# REUN_468349_001_PSU_Board_12B_Interface.net
KiCad netlist of a schematic drawn in Altium Designer
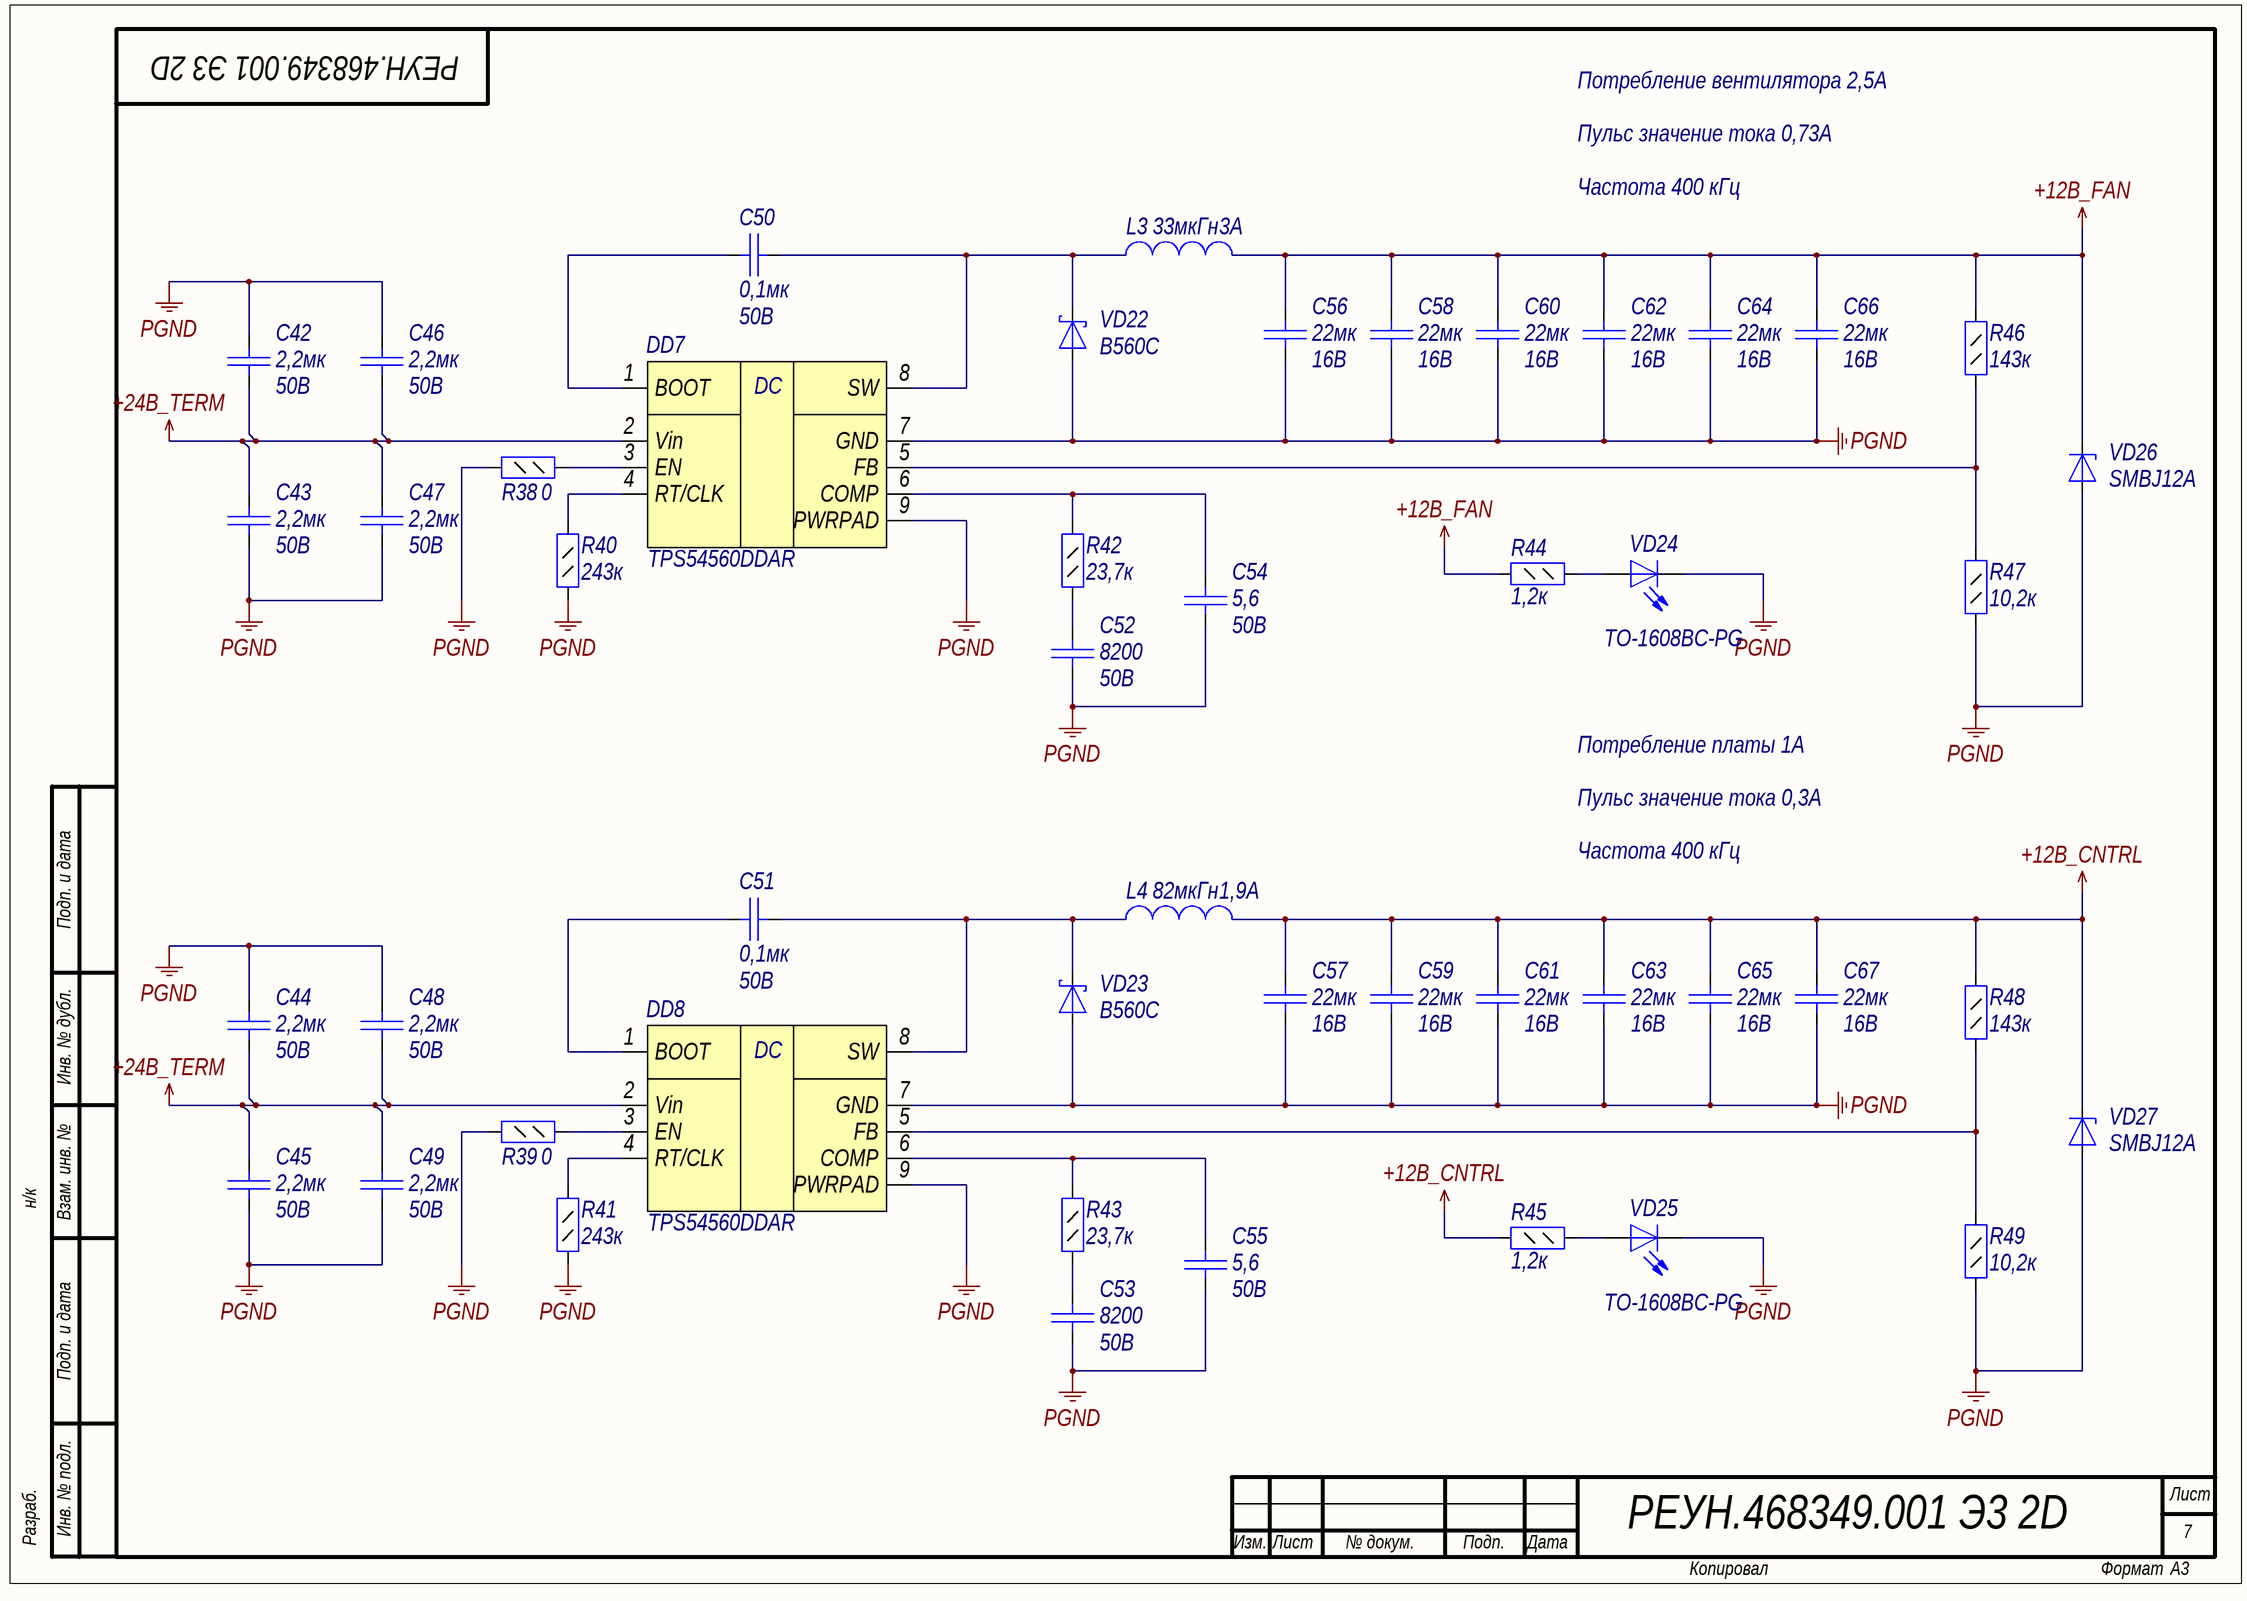
[diagram p0: REUN.468349.001_PSU_Board_12B_Interface.SchDoc]

(export (version "E")
  (design (tool "Eeschema 10.0.6"))
  (components
    (comp (ref "C42")
      (value "2,2мк")
      (footprint "C1206")
      (description "Конденсатор")
      (fields (field (name "VOLTAGE") "50B") (field (name "PART NUMBER") "CL31B225KBHNNNE"))
      (libsource (lib "MOP44") (part "Capacitor"))
    )
    (comp (ref "C43")
      (value "2,2мк")
      (footprint "C1206")
      (description "Конденсатор")
      (fields (field (name "VOLTAGE") "50B") (field (name "PART NUMBER") "CL31B225KBHNNNE"))
      (libsource (lib "MOP44") (part "Capacitor"))
    )
    (comp (ref "C44")
      (value "2,2мк")
      (footprint "C1206")
      (description "Конденсатор")
      (fields (field (name "VOLTAGE") "50B") (field (name "PART NUMBER") "CL31B225KBHNNNE"))
      (libsource (lib "MOP44") (part "Capacitor"))
    )
    (comp (ref "C45")
      (value "2,2мк")
      (footprint "C1206")
      (description "Конденсатор")
      (fields (field (name "VOLTAGE") "50B") (field (name "PART NUMBER") "CL31B225KBHNNNE"))
      (libsource (lib "MOP44") (part "Capacitor"))
    )
    (comp (ref "C46")
      (value "2,2мк")
      (footprint "C1206")
      (description "Конденсатор")
      (fields (field (name "VOLTAGE") "50B") (field (name "PART NUMBER") "CL31B225KBHNNNE"))
      (libsource (lib "MOP44") (part "Capacitor"))
    )
    (comp (ref "C47")
      (value "2,2мк")
      (footprint "C1206")
      (description "Конденсатор")
      (fields (field (name "VOLTAGE") "50B") (field (name "PART NUMBER") "CL31B225KBHNNNE"))
      (libsource (lib "MOP44") (part "Capacitor"))
    )
    (comp (ref "C48")
      (value "2,2мк")
      (footprint "C1206")
      (description "Конденсатор")
      (fields (field (name "VOLTAGE") "50B") (field (name "PART NUMBER") "CL31B225KBHNNNE"))
      (libsource (lib "MOP44") (part "Capacitor"))
    )
    (comp (ref "C49")
      (value "2,2мк")
      (footprint "C1206")
      (description "Конденсатор")
      (fields (field (name "VOLTAGE") "50B") (field (name "PART NUMBER") "CL31B225KBHNNNE"))
      (libsource (lib "MOP44") (part "Capacitor"))
    )
    (comp (ref "C50")
      (value "0,1мк")
      (footprint "C0805")
      (description "Конденсатор")
      (fields (field (name "VOLTAGE") "50B") (field (name "PART NUMBER") "GRM21BR71H104KA01K"))
      (libsource (lib "MOP44") (part "Capacitor"))
    )
    (comp (ref "C51")
      (value "0,1мк")
      (footprint "C0805")
      (description "Конденсатор")
      (fields (field (name "VOLTAGE") "50B") (field (name "PART NUMBER") "GRM21BR71H104KA01K"))
      (libsource (lib "MOP44") (part "Capacitor"))
    )
    (comp (ref "C52")
      (value "8200")
      (footprint "C0805")
      (description "Конденсатор")
      (fields (field (name "VOLTAGE") "50В") (field (name "PART NUMBER") "GRM216R71H822KA01D"))
      (libsource (lib "MOP44") (part "Capacitor"))
    )
    (comp (ref "C53")
      (value "8200")
      (footprint "C0805")
      (description "Конденсатор")
      (fields (field (name "VOLTAGE") "50В") (field (name "PART NUMBER") "GRM216R71H822KA01D"))
      (libsource (lib "MOP44") (part "Capacitor"))
    )
    (comp (ref "C54")
      (value "5,6")
      (footprint "C0805")
      (description "Конденсатор")
      (fields (field (name "VOLTAGE") "50B") (field (name "PART NUMBER") "CL21C5R6CBANNNC"))
      (libsource (lib "MOP44") (part "Capacitor"))
    )
    (comp (ref "C55")
      (value "5,6")
      (footprint "C0805")
      (description "Конденсатор")
      (fields (field (name "VOLTAGE") "50B") (field (name "PART NUMBER") "CL21C5R6CBANNNC"))
      (libsource (lib "MOP44") (part "Capacitor"))
    )
    (comp (ref "C56")
      (value "22мк")
      (footprint "C1210")
      (description "Конденсатор")
      (fields (field (name "VOLTAGE") "16B") (field (name "PART NUMBER") "CL32B226KOJNNNE"))
      (libsource (lib "MOP44") (part "Capacitor"))
    )
    (comp (ref "C57")
      (value "22мк")
      (footprint "C1210")
      (description "Конденсатор")
      (fields (field (name "VOLTAGE") "16B") (field (name "PART NUMBER") "CL32B226KOJNNNE"))
      (libsource (lib "MOP44") (part "Capacitor"))
    )
    (comp (ref "C58")
      (value "22мк")
      (footprint "C1210")
      (description "Конденсатор")
      (fields (field (name "VOLTAGE") "16B") (field (name "PART NUMBER") "CL32B226KOJNNNE"))
      (libsource (lib "MOP44") (part "Capacitor"))
    )
    (comp (ref "C59")
      (value "22мк")
      (footprint "C1210")
      (description "Конденсатор")
      (fields (field (name "VOLTAGE") "16B") (field (name "PART NUMBER") "CL32B226KOJNNNE"))
      (libsource (lib "MOP44") (part "Capacitor"))
    )
    (comp (ref "C60")
      (value "22мк")
      (footprint "C1210")
      (description "Конденсатор")
      (fields (field (name "VOLTAGE") "16B") (field (name "PART NUMBER") "CL32B226KOJNNNE"))
      (libsource (lib "MOP44") (part "Capacitor"))
    )
    (comp (ref "C61")
      (value "22мк")
      (footprint "C1210")
      (description "Конденсатор")
      (fields (field (name "VOLTAGE") "16B") (field (name "PART NUMBER") "CL32B226KOJNNNE"))
      (libsource (lib "MOP44") (part "Capacitor"))
    )
    (comp (ref "C62")
      (value "22мк")
      (footprint "C1210")
      (description "Конденсатор")
      (fields (field (name "VOLTAGE") "16B") (field (name "PART NUMBER") "CL32B226KOJNNNE"))
      (libsource (lib "MOP44") (part "Capacitor"))
    )
    (comp (ref "C63")
      (value "22мк")
      (footprint "C1210")
      (description "Конденсатор")
      (fields (field (name "VOLTAGE") "16B") (field (name "PART NUMBER") "CL32B226KOJNNNE"))
      (libsource (lib "MOP44") (part "Capacitor"))
    )
    (comp (ref "C64")
      (value "22мк")
      (footprint "C1210")
      (description "Конденсатор")
      (fields (field (name "VOLTAGE") "16B") (field (name "PART NUMBER") "CL32B226KOJNNNE"))
      (libsource (lib "MOP44") (part "Capacitor"))
    )
    (comp (ref "C65")
      (value "22мк")
      (footprint "C1210")
      (description "Конденсатор")
      (fields (field (name "VOLTAGE") "16B") (field (name "PART NUMBER") "CL32B226KOJNNNE"))
      (libsource (lib "MOP44") (part "Capacitor"))
    )
    (comp (ref "C66")
      (value "22мк")
      (footprint "C1210")
      (description "Конденсатор")
      (fields (field (name "VOLTAGE") "16B") (field (name "PART NUMBER") "CL32B226KOJNNNE"))
      (libsource (lib "MOP44") (part "Capacitor"))
    )
    (comp (ref "C67")
      (value "22мк")
      (footprint "C1210")
      (description "Конденсатор")
      (fields (field (name "VOLTAGE") "16B") (field (name "PART NUMBER") "CL32B226KOJNNNE"))
      (libsource (lib "MOP44") (part "Capacitor"))
    )
    (comp (ref "DD7")
      (value "TPS54560DDAR")
      (footprint "SO Powerpad8")
      (description "5-A, Wide Input Range, Step-Down Converter")
      (fields (field (name "MANUFACTURER") "Texas Instruments"))
      (libsource (lib "MOP44") (part "TPS54560"))
    )
    (comp (ref "DD8")
      (value "TPS54560DDAR")
      (footprint "SO Powerpad8")
      (description "5-A, Wide Input Range, Step-Down Converter")
      (fields (field (name "MANUFACTURER") "Texas Instruments"))
      (libsource (lib "MOP44") (part "TPS54560"))
    )
    (comp (ref "L3")
      (value "33мкГн")
      (footprint "IND_12.5x12.5")
      (description "EMI Suppression Filter")
      (fields
        (field (name "RATED CURRENT") "3A")
        (field (name "PART NUMBER") "B82477G4333M000")
        (field (name "Comment") "Inductor")
      )
      (libsource (lib "MOP44") (part "Inductor"))
    )
    (comp (ref "L4")
      (value "82мкГн")
      (footprint "IND_12.5x12.5")
      (description "EMI Suppression Filter")
      (fields
        (field (name "RATED CURRENT") "1,9A")
        (field (name "PART NUMBER") "B82477G4823M000")
        (field (name "Comment") "Inductor")
      )
      (libsource (lib "MOP44") (part "Inductor"))
    )
    (comp (ref "R38")
      (value "0")
      (footprint "R0805")
      (description "Резистор")
      (fields (field (name "PART NUMBER") "RC0805FR-070RL") (field (name "POWER") "0,125Вт"))
      (libsource (lib "REUN.468349.001_PSU_Board") (part "res25"))
    )
    (comp (ref "R39")
      (value "0")
      (footprint "R0805")
      (description "Резистор")
      (fields (field (name "PART NUMBER") "RC0805FR-070RL") (field (name "POWER") "0,125Вт"))
      (libsource (lib "REUN.468349.001_PSU_Board") (part "res25"))
    )
    (comp (ref "R40")
      (value "243к")
      (footprint "R0805")
      (description "Резистор")
      (fields (field (name "PART NUMBER") "RC0805FR-07243KL") (field (name "POWER") "0,125Вт"))
      (libsource (lib "MOP44") (part "Resistor_0,125Вт"))
    )
    (comp (ref "R41")
      (value "243к")
      (footprint "R0805")
      (description "Резистор")
      (fields (field (name "PART NUMBER") "RC0805FR-07243KL") (field (name "POWER") "0,125Вт"))
      (libsource (lib "MOP44") (part "Resistor_0,125Вт"))
    )
    (comp (ref "R42")
      (value "23,7к")
      (footprint "R0805")
      (description "Резистор")
      (fields (field (name "PART NUMBER") "RC0805FR-0723K7L") (field (name "POWER") "0,125Вт"))
      (libsource (lib "MOP44") (part "Resistor_0,125Вт"))
    )
    (comp (ref "R43")
      (value "23,7к")
      (footprint "R0805")
      (description "Резистор")
      (fields (field (name "PART NUMBER") "RC0805FR-0723K7L") (field (name "POWER") "0,125Вт"))
      (libsource (lib "MOP44") (part "Resistor_0,125Вт"))
    )
    (comp (ref "R44")
      (value "1,2к")
      (footprint "R0805")
      (description "Резистор")
      (fields (field (name "PART NUMBER") "RC0805FR-071K2") (field (name "POWER") "0,125Вт"))
      (libsource (lib "") (part "Resistor_0,125Вт_1"))
    )
    (comp (ref "R45")
      (value "1,2к")
      (footprint "R0805")
      (description "Резистор")
      (fields (field (name "PART NUMBER") "RC0805FR-071K2") (field (name "POWER") "0,125Вт"))
      (libsource (lib "") (part "Resistor_0,125Вт_1"))
    )
    (comp (ref "R46")
      (value "143к")
      (footprint "R0805")
      (description "Резистор")
      (fields (field (name "PART NUMBER") "RC0805FR-07143KL") (field (name "POWER") "0,125Вт"))
      (libsource (lib "MOP44") (part "Resistor_0,125Вт"))
    )
    (comp (ref "R47")
      (value "10,2к")
      (footprint "R0805")
      (description "Резистор")
      (fields (field (name "PART NUMBER") "RC0805FR-0710K2L") (field (name "POWER") "0,125Вт"))
      (libsource (lib "MOP44") (part "Resistor_0,125Вт"))
    )
    (comp (ref "R48")
      (value "143к")
      (footprint "R0805")
      (description "Резистор")
      (fields (field (name "PART NUMBER") "RC0805FR-07143KL") (field (name "POWER") "0,125Вт"))
      (libsource (lib "MOP44") (part "Resistor_0,125Вт"))
    )
    (comp (ref "R49")
      (value "10,2к")
      (footprint "R0805")
      (description "Резистор")
      (fields (field (name "PART NUMBER") "RC0805FR-0710K2L") (field (name "POWER") "0,125Вт"))
      (libsource (lib "MOP44") (part "Resistor_0,125Вт"))
    )
    (comp (ref "VD22")
      (value "B560C")
      (footprint "SMC")
      (description "Диод Шоттки")
      (libsource (lib "MOP44") (part "DiodeSchottky"))
    )
    (comp (ref "VD23")
      (value "B560C")
      (footprint "SMC")
      (description "Диод Шоттки")
      (libsource (lib "MOP44") (part "DiodeSchottky"))
    )
    (comp (ref "VD24")
      (value "TO-1608BC-PG")
      (footprint "L_0603_GREEN")
      (description "Светодиод")
      (libsource (lib "MOP44") (part "LED"))
    )
    (comp (ref "VD25")
      (value "TO-1608BC-PG")
      (footprint "L_0603_GREEN")
      (description "Светодиод")
      (libsource (lib "MOP44") (part "LED"))
    )
    (comp (ref "VD26")
      (value "SMBJ12A")
      (footprint "SMB")
      (description "Cтабилитрон (лавинный выпрямительный диод) односторонний")
      (libsource (lib "MOP44") (part "DiodeZener"))
    )
    (comp (ref "VD27")
      (value "SMBJ12A")
      (footprint "SMB")
      (description "Cтабилитрон (лавинный выпрямительный диод) односторонний")
      (libsource (lib "MOP44") (part "DiodeZener"))
    )
  )
  (nets
    (net (code "1") (name "+12B_CNTRL") (class "Default")
      (node (ref "C57") (pin "2") (pinfunction "2_2") (pintype "passive"))
      (node (ref "C59") (pin "2") (pinfunction "2_2") (pintype "passive"))
      (node (ref "C61") (pin "2") (pinfunction "2_2") (pintype "passive"))
      (node (ref "C63") (pin "2") (pinfunction "2_2") (pintype "passive"))
      (node (ref "C65") (pin "2") (pinfunction "2_2") (pintype "passive"))
      (node (ref "C67") (pin "2") (pinfunction "2_2") (pintype "passive"))
      (node (ref "L4") (pin "2") (pinfunction "2_2") (pintype "passive"))
      (node (ref "R45") (pin "2") (pinfunction "2_2") (pintype "passive"))
      (node (ref "R48") (pin "2") (pinfunction "2_2") (pintype "passive"))
      (node (ref "VD27") (pin "1") (pinfunction "K_1") (pintype "passive"))
    )
    (net (code "2") (name "+12B_FAN") (class "Default")
      (node (ref "C56") (pin "2") (pinfunction "2_2") (pintype "passive"))
      (node (ref "C58") (pin "2") (pinfunction "2_2") (pintype "passive"))
      (node (ref "C60") (pin "2") (pinfunction "2_2") (pintype "passive"))
      (node (ref "C62") (pin "2") (pinfunction "2_2") (pintype "passive"))
      (node (ref "C64") (pin "2") (pinfunction "2_2") (pintype "passive"))
      (node (ref "C66") (pin "2") (pinfunction "2_2") (pintype "passive"))
      (node (ref "L3") (pin "2") (pinfunction "2_2") (pintype "passive"))
      (node (ref "R44") (pin "2") (pinfunction "2_2") (pintype "passive"))
      (node (ref "R46") (pin "2") (pinfunction "2_2") (pintype "passive"))
      (node (ref "VD26") (pin "1") (pinfunction "K_1") (pintype "passive"))
    )
    (net (code "3") (name "+24B_TERM") (class "Default")
      (node (ref "C42") (pin "1") (pinfunction "1_1") (pintype "passive"))
      (node (ref "C43") (pin "2") (pinfunction "2_2") (pintype "passive"))
      (node (ref "C44") (pin "1") (pinfunction "1_1") (pintype "passive"))
      (node (ref "C45") (pin "2") (pinfunction "2_2") (pintype "passive"))
      (node (ref "C46") (pin "1") (pinfunction "1_1") (pintype "passive"))
      (node (ref "C47") (pin "2") (pinfunction "2_2") (pintype "passive"))
      (node (ref "C48") (pin "1") (pinfunction "1_1") (pintype "passive"))
      (node (ref "C49") (pin "2") (pinfunction "2_2") (pintype "passive"))
      (node (ref "DD7") (pin "2") (pinfunction "Vin_2") (pintype "passive"))
      (node (ref "DD8") (pin "2") (pinfunction "Vin_2") (pintype "passive"))
    )
    (net (code "4") (name "Net-(C52-Pad2)") (class "Default")
      (node (ref "C52") (pin "2") (pinfunction "2_2") (pintype "passive"))
      (node (ref "R42") (pin "1") (pinfunction "1_1") (pintype "passive"))
    )
    (net (code "5") (name "Net-(C53-Pad2)") (class "Default")
      (node (ref "C53") (pin "2") (pinfunction "2_2") (pintype "passive"))
      (node (ref "R43") (pin "1") (pinfunction "1_1") (pintype "passive"))
    )
    (net (code "6") (name "Net-(DD7-BOOT)") (class "Default")
      (node (ref "C50") (pin "2") (pinfunction "2_2") (pintype "passive"))
      (node (ref "DD7") (pin "1") (pinfunction "BOOT_1") (pintype "passive"))
    )
    (net (code "7") (name "Net-(DD7-COMP)") (class "Default")
      (node (ref "C54") (pin "2") (pinfunction "2_2") (pintype "passive"))
      (node (ref "DD7") (pin "6") (pinfunction "COMP_6") (pintype "passive"))
      (node (ref "R42") (pin "2") (pinfunction "2_2") (pintype "passive"))
    )
    (net (code "8") (name "Net-(DD7-EN)") (class "Default")
      (node (ref "DD7") (pin "3") (pinfunction "EN_3") (pintype "passive"))
      (node (ref "R38") (pin "1") (pinfunction "1_1") (pintype "passive"))
    )
    (net (code "9") (name "Net-(DD7-FB)") (class "Default")
      (node (ref "DD7") (pin "5") (pinfunction "FB_5") (pintype "passive"))
      (node (ref "R46") (pin "1") (pinfunction "1_1") (pintype "passive"))
      (node (ref "R47") (pin "2") (pinfunction "2_2") (pintype "passive"))
    )
    (net (code "10") (name "Net-(DD7-RT{slash}CLK)") (class "Default")
      (node (ref "DD7") (pin "4") (pinfunction "RT/CLK_4") (pintype "passive"))
      (node (ref "R40") (pin "2") (pinfunction "2_2") (pintype "passive"))
    )
    (net (code "11") (name "Net-(DD7-SW)") (class "Default")
      (node (ref "C50") (pin "1") (pinfunction "1_1") (pintype "passive"))
      (node (ref "DD7") (pin "8") (pinfunction "SW_8") (pintype "passive"))
      (node (ref "L3") (pin "1") (pinfunction "1_1") (pintype "passive"))
      (node (ref "VD22") (pin "1") (pinfunction "K_1") (pintype "passive"))
    )
    (net (code "12") (name "Net-(DD8-BOOT)") (class "Default")
      (node (ref "C51") (pin "2") (pinfunction "2_2") (pintype "passive"))
      (node (ref "DD8") (pin "1") (pinfunction "BOOT_1") (pintype "passive"))
    )
    (net (code "13") (name "Net-(DD8-COMP)") (class "Default")
      (node (ref "C55") (pin "2") (pinfunction "2_2") (pintype "passive"))
      (node (ref "DD8") (pin "6") (pinfunction "COMP_6") (pintype "passive"))
      (node (ref "R43") (pin "2") (pinfunction "2_2") (pintype "passive"))
    )
    (net (code "14") (name "Net-(DD8-EN)") (class "Default")
      (node (ref "DD8") (pin "3") (pinfunction "EN_3") (pintype "passive"))
      (node (ref "R39") (pin "1") (pinfunction "1_1") (pintype "passive"))
    )
    (net (code "15") (name "Net-(DD8-FB)") (class "Default")
      (node (ref "DD8") (pin "5") (pinfunction "FB_5") (pintype "passive"))
      (node (ref "R48") (pin "1") (pinfunction "1_1") (pintype "passive"))
      (node (ref "R49") (pin "2") (pinfunction "2_2") (pintype "passive"))
    )
    (net (code "16") (name "Net-(DD8-RT{slash}CLK)") (class "Default")
      (node (ref "DD8") (pin "4") (pinfunction "RT/CLK_4") (pintype "passive"))
      (node (ref "R41") (pin "2") (pinfunction "2_2") (pintype "passive"))
    )
    (net (code "17") (name "Net-(DD8-SW)") (class "Default")
      (node (ref "C51") (pin "1") (pinfunction "1_1") (pintype "passive"))
      (node (ref "DD8") (pin "8") (pinfunction "SW_8") (pintype "passive"))
      (node (ref "L4") (pin "1") (pinfunction "1_1") (pintype "passive"))
      (node (ref "VD23") (pin "1") (pinfunction "K_1") (pintype "passive"))
    )
    (net (code "18") (name "Net-(VD24-A)") (class "Default")
      (node (ref "R44") (pin "1") (pinfunction "1_1") (pintype "passive"))
      (node (ref "VD24") (pin "2") (pinfunction "A_2") (pintype "passive"))
    )
    (net (code "19") (name "Net-(VD25-A)") (class "Default")
      (node (ref "R45") (pin "1") (pinfunction "1_1") (pintype "passive"))
      (node (ref "VD25") (pin "2") (pinfunction "A_2") (pintype "passive"))
    )
    (net (code "20") (name "PGND") (class "Default")
      (node (ref "C42") (pin "2") (pinfunction "2_2") (pintype "passive"))
      (node (ref "C43") (pin "1") (pinfunction "1_1") (pintype "passive"))
      (node (ref "C44") (pin "2") (pinfunction "2_2") (pintype "passive"))
      (node (ref "C45") (pin "1") (pinfunction "1_1") (pintype "passive"))
      (node (ref "C46") (pin "2") (pinfunction "2_2") (pintype "passive"))
      (node (ref "C47") (pin "1") (pinfunction "1_1") (pintype "passive"))
      (node (ref "C48") (pin "2") (pinfunction "2_2") (pintype "passive"))
      (node (ref "C49") (pin "1") (pinfunction "1_1") (pintype "passive"))
      (node (ref "C52") (pin "1") (pinfunction "1_1") (pintype "passive"))
      (node (ref "C53") (pin "1") (pinfunction "1_1") (pintype "passive"))
      (node (ref "C54") (pin "1") (pinfunction "1_1") (pintype "passive"))
      (node (ref "C55") (pin "1") (pinfunction "1_1") (pintype "passive"))
      (node (ref "C56") (pin "1") (pinfunction "1_1") (pintype "passive"))
      (node (ref "C57") (pin "1") (pinfunction "1_1") (pintype "passive"))
      (node (ref "C58") (pin "1") (pinfunction "1_1") (pintype "passive"))
      (node (ref "C59") (pin "1") (pinfunction "1_1") (pintype "passive"))
      (node (ref "C60") (pin "1") (pinfunction "1_1") (pintype "passive"))
      (node (ref "C61") (pin "1") (pinfunction "1_1") (pintype "passive"))
      (node (ref "C62") (pin "1") (pinfunction "1_1") (pintype "passive"))
      (node (ref "C63") (pin "1") (pinfunction "1_1") (pintype "passive"))
      (node (ref "C64") (pin "1") (pinfunction "1_1") (pintype "passive"))
      (node (ref "C65") (pin "1") (pinfunction "1_1") (pintype "passive"))
      (node (ref "C66") (pin "1") (pinfunction "1_1") (pintype "passive"))
      (node (ref "C67") (pin "1") (pinfunction "1_1") (pintype "passive"))
      (node (ref "DD7") (pin "7") (pinfunction "GND_7") (pintype "passive"))
      (node (ref "DD7") (pin "9") (pinfunction "PWRPAD_9") (pintype "passive"))
      (node (ref "DD8") (pin "7") (pinfunction "GND_7") (pintype "passive"))
      (node (ref "DD8") (pin "9") (pinfunction "PWRPAD_9") (pintype "passive"))
      (node (ref "R38") (pin "2") (pinfunction "2_2") (pintype "passive"))
      (node (ref "R39") (pin "2") (pinfunction "2_2") (pintype "passive"))
      (node (ref "R40") (pin "1") (pinfunction "1_1") (pintype "passive"))
      (node (ref "R41") (pin "1") (pinfunction "1_1") (pintype "passive"))
      (node (ref "R47") (pin "1") (pinfunction "1_1") (pintype "passive"))
      (node (ref "R49") (pin "1") (pinfunction "1_1") (pintype "passive"))
      (node (ref "VD22") (pin "2") (pinfunction "A_2") (pintype "passive"))
      (node (ref "VD23") (pin "2") (pinfunction "A_2") (pintype "passive"))
      (node (ref "VD24") (pin "1") (pinfunction "K_1") (pintype "passive"))
      (node (ref "VD25") (pin "1") (pinfunction "K_1") (pintype "passive"))
      (node (ref "VD26") (pin "2") (pinfunction "A_2") (pintype "passive"))
      (node (ref "VD27") (pin "2") (pinfunction "A_2") (pintype "passive"))
    )
  )
)
